# LN2_Autofill_Controller.net
KiCad netlist of a schematic drawn in EAGLE
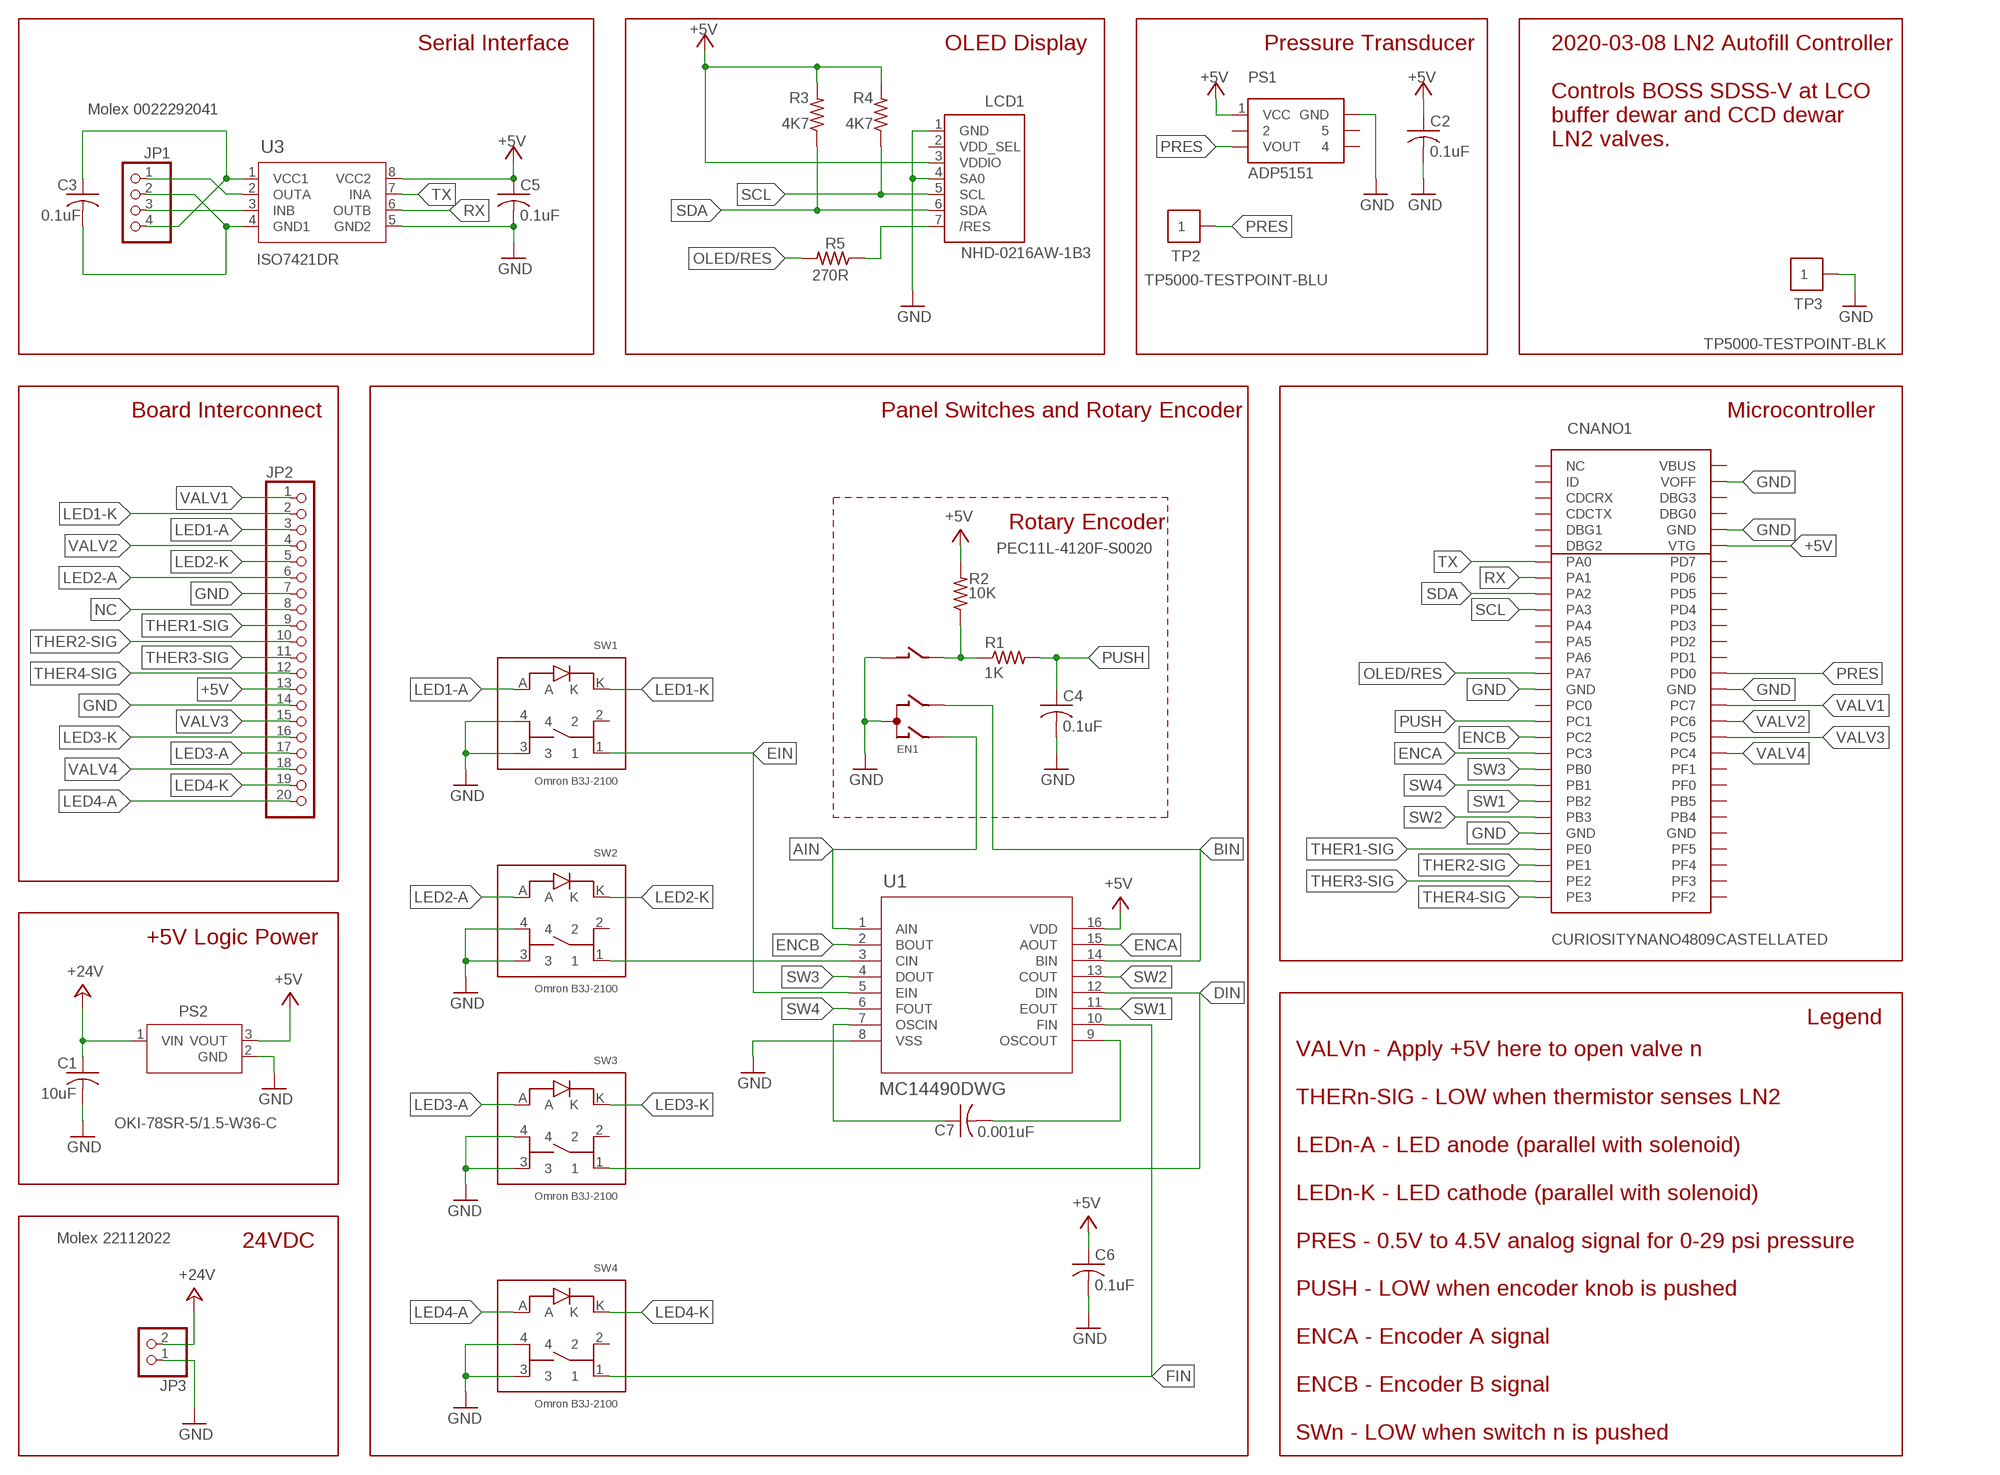
[diagram p0: schematic, sheet 1]

(export (version "E")
  (design (tool "Eeschema 10.0.6"))
  (components
    (comp (ref "C1")
      (value "10uF")
      (footprint "eagle-import:C1210K")
      (libsource (lib "eagle-import") (part "C-USC1210K"))
    )
    (comp (ref "C2")
      (value "0.1uF")
      (footprint "eagle-import:C0805")
      (libsource (lib "eagle-import") (part "C-USC0805"))
    )
    (comp (ref "C3")
      (value "0.1uF")
      (footprint "eagle-import:C0805")
      (libsource (lib "eagle-import") (part "C-USC0805"))
    )
    (comp (ref "C4")
      (value "0.1uF")
      (footprint "eagle-import:C0805")
      (libsource (lib "eagle-import") (part "C-USC0805"))
    )
    (comp (ref "C5")
      (value "0.1uF")
      (footprint "eagle-import:C0805")
      (libsource (lib "eagle-import") (part "C-USC0805"))
    )
    (comp (ref "C6")
      (value "0.1uF")
      (footprint "eagle-import:C0805")
      (libsource (lib "eagle-import") (part "C-USC0805"))
    )
    (comp (ref "C7")
      (value "0.001uF")
      (footprint "eagle-import:C0805")
      (libsource (lib "eagle-import") (part "C-USC0805"))
    )
    (comp (ref "CNANO1")
      (value "CURIOSITYNANO4809CASTELLATED")
      (footprint "eagle-import:CURIOSITYNANO4809CASTELLATED")
      (libsource (lib "eagle-import") (part "CURIOSITYNANO4809CASTELLATED"))
    )
    (comp (ref "EN1")
      (value "PEC11L-4120F-S0020")
      (footprint "eagle-import:ENC-BOURNES-PEC11L")
      (libsource (lib "eagle-import") (part "ENC-BOURNES-PEC11L"))
    )
    (comp (ref "JP1")
      (value "Molex 0022292041")
      (footprint "eagle-import:MOLEX-04-VERT")
      (libsource (lib "eagle-import") (part "PINHD-1X4MOLEX-04-VERT"))
    )
    (comp (ref "JP2")
      (value "PINHD-1X20")
      (footprint "eagle-import:1X20")
      (libsource (lib "eagle-import") (part "PINHD-1X20"))
    )
    (comp (ref "JP3")
      (value "Molex 22112022")
      (footprint "eagle-import:MOLEX-02-VERT")
      (libsource (lib "eagle-import") (part "PINHD-1X2MOLEX-02-VERT"))
    )
    (comp (ref "LCD1")
      (value "NHD-0216AW-1B3")
      (footprint "eagle-import:LCD-NEWHAVEN-16X2")
      (libsource (lib "eagle-import") (part "LCD-NEWHAVEN-16X2"))
    )
    (comp (ref "PS1")
      (value "ADP5151")
      (footprint "eagle-import:PRESSURE-SENSOR-ADP5151")
      (libsource (lib "eagle-import") (part "PRESSURE-SENSOR-ADP5151"))
    )
    (comp (ref "PS2")
      (value "OKI-78SR-5/1.5-W36-C")
      (footprint "eagle-import:CONV_OKI-78SR-5_1.5-W36-C")
      (fields
        (field (name "DIGI-KEY_PART_NUMBER") "811-2196-5-ND")
        (field (name "MF") "Murata Power Solutions Inc.")
      )
      (libsource (lib "eagle-import") (part "OKI-78SR-5/1.5-W36-C"))
    )
    (comp (ref "R1")
      (value "1K")
      (footprint "eagle-import:R0805")
      (libsource (lib "eagle-import") (part "R-US_R0805"))
    )
    (comp (ref "R2")
      (value "10K")
      (footprint "eagle-import:R0805")
      (libsource (lib "eagle-import") (part "R-US_R0805"))
    )
    (comp (ref "R3")
      (value "4K7")
      (footprint "eagle-import:R0805")
      (libsource (lib "eagle-import") (part "R-US_R0805"))
    )
    (comp (ref "R4")
      (value "4K7")
      (footprint "eagle-import:R0805")
      (libsource (lib "eagle-import") (part "R-US_R0805"))
    )
    (comp (ref "R5")
      (value "270R")
      (footprint "eagle-import:R0805")
      (libsource (lib "eagle-import") (part "R-US_R0805"))
    )
    (comp (ref "SW1")
      (value "Omron B3J-2100")
      (footprint "eagle-import:SWITCH-OMRON-B3J-1LED")
      (libsource (lib "eagle-import") (part "SWITCH-OMRON-B3J-1LED"))
    )
    (comp (ref "SW2")
      (value "Omron B3J-2100")
      (footprint "eagle-import:SWITCH-OMRON-B3J-1LED")
      (libsource (lib "eagle-import") (part "SWITCH-OMRON-B3J-1LED"))
    )
    (comp (ref "SW3")
      (value "Omron B3J-2100")
      (footprint "eagle-import:SWITCH-OMRON-B3J-1LED")
      (libsource (lib "eagle-import") (part "SWITCH-OMRON-B3J-1LED"))
    )
    (comp (ref "SW4")
      (value "Omron B3J-2100")
      (footprint "eagle-import:SWITCH-OMRON-B3J-1LED")
      (libsource (lib "eagle-import") (part "SWITCH-OMRON-B3J-1LED"))
    )
    (comp (ref "TP2")
      (value "TP5000-TESTPOINT-BLU")
      (footprint "eagle-import:TP5000-TESTPOINT-BLU")
      (libsource (lib "eagle-import") (part "TP5000-TESTPOINT-BLU"))
    )
    (comp (ref "TP3")
      (value "TP5000-TESTPOINT-BLK")
      (footprint "eagle-import:TP5000-TESTPOINT-BLK")
      (libsource (lib "eagle-import") (part "TP5000-TESTPOINT-BLK"))
    )
    (comp (ref "U1")
      (value "MC14490DWG")
      (footprint "eagle-import:SOIC127P1030X265-16N")
      (libsource (lib "eagle-import") (part "DEBOUNCER-MC14490DWGSOIC-16-WB"))
    )
    (comp (ref "U3")
      (value "ISO7421DR")
      (footprint "eagle-import:SOIC127P599X175-8N")
      (libsource (lib "eagle-import") (part "ISO7421DRTI-SOIC-D8"))
    )
  )
  (nets
    (net (code "1") (name "+5V") (class "Default")
      (node (ref "C2") (pin "1") (pinfunction "1_1") (pintype "passive"))
      (node (ref "C5") (pin "1") (pinfunction "1_1") (pintype "passive"))
      (node (ref "C6") (pin "1") (pinfunction "1_1") (pintype "passive"))
      (node (ref "CNANO1") (pin "VTG") (pinfunction "VTG_VTG") (pintype "bidirectional"))
      (node (ref "JP2") (pin "13") (pinfunction "13_13") (pintype "passive"))
      (node (ref "LCD1") (pin "3") (pinfunction "VDDIO_3") (pintype "bidirectional"))
      (node (ref "PS1") (pin "1") (pinfunction "VCC_1") (pintype "bidirectional"))
      (node (ref "PS2") (pin "3") (pinfunction "VOUT_3") (pintype "power_in"))
      (node (ref "R2") (pin "2") (pinfunction "2_2") (pintype "passive"))
      (node (ref "R3") (pin "2") (pinfunction "2_2") (pintype "passive"))
      (node (ref "R4") (pin "2") (pinfunction "2_2") (pintype "passive"))
      (node (ref "U1") (pin "16") (pinfunction "VDD_16") (pintype "power_in"))
      (node (ref "U3") (pin "8") (pinfunction "VCC2_8") (pintype "power_in"))
    )
    (net (code "2") (name "+24V") (class "Default")
      (node (ref "C1") (pin "1") (pinfunction "1_1") (pintype "passive"))
      (node (ref "JP3") (pin "2") (pinfunction "2_2") (pintype "passive"))
      (node (ref "PS2") (pin "1") (pinfunction "VIN_1") (pintype "input"))
    )
    (net (code "3") (name "AIN") (class "Default")
      (node (ref "EN1") (pin "A") (pinfunction "A_A") (pintype "passive"))
      (node (ref "U1") (pin "1") (pinfunction "AIN_1") (pintype "input"))
    )
    (net (code "4") (name "BIN") (class "Default")
      (node (ref "EN1") (pin "B") (pinfunction "B_B") (pintype "passive"))
      (node (ref "U1") (pin "14") (pinfunction "BIN_14") (pintype "input"))
    )
    (net (code "5") (name "DIN") (class "Default")
      (node (ref "SW3") (pin "1") (pinfunction "1_1") (pintype "bidirectional"))
      (node (ref "U1") (pin "12") (pinfunction "DIN_12") (pintype "input"))
    )
    (net (code "6") (name "EIN") (class "Default")
      (node (ref "SW1") (pin "1") (pinfunction "1_1") (pintype "bidirectional"))
      (node (ref "U1") (pin "5") (pinfunction "EIN_5") (pintype "input"))
    )
    (net (code "7") (name "ENCA") (class "Default")
      (node (ref "CNANO1") (pin "PC3") (pinfunction "PC3_PC3") (pintype "bidirectional"))
      (node (ref "U1") (pin "15") (pinfunction "AOUT_15") (pintype "output"))
    )
    (net (code "8") (name "ENCB") (class "Default")
      (node (ref "CNANO1") (pin "PC2") (pinfunction "PC2_PC2") (pintype "bidirectional"))
      (node (ref "U1") (pin "2") (pinfunction "BOUT_2") (pintype "output"))
    )
    (net (code "9") (name "FIN") (class "Default")
      (node (ref "SW4") (pin "1") (pinfunction "1_1") (pintype "bidirectional"))
      (node (ref "U1") (pin "10") (pinfunction "FIN_10") (pintype "input"))
    )
    (net (code "10") (name "GND") (class "Default")
      (node (ref "C1") (pin "2") (pinfunction "2_2") (pintype "passive"))
      (node (ref "C2") (pin "2") (pinfunction "2_2") (pintype "passive"))
      (node (ref "C4") (pin "2") (pinfunction "2_2") (pintype "passive"))
      (node (ref "C5") (pin "2") (pinfunction "2_2") (pintype "passive"))
      (node (ref "C6") (pin "2") (pinfunction "2_2") (pintype "passive"))
      (node (ref "CNANO1") (pin "GND15") (pinfunction "GND_GND15") (pintype "bidirectional"))
      (node (ref "CNANO1") (pin "GND24") (pinfunction "GND_GND24") (pintype "bidirectional"))
      (node (ref "CNANO1") (pin "GND42") (pinfunction "GND_GND42") (pintype "bidirectional"))
      (node (ref "CNANO1") (pin "GND52") (pinfunction "GND_GND52") (pintype "bidirectional"))
      (node (ref "CNANO1") (pin "VOFF") (pinfunction "VOFF_VOFF") (pintype "bidirectional"))
      (node (ref "EN1") (pin "2") (pinfunction "C1_2") (pintype "passive"))
      (node (ref "EN1") (pin "C") (pinfunction "C_C") (pintype "passive"))
      (node (ref "JP2") (pin "14") (pinfunction "14_14") (pintype "passive"))
      (node (ref "JP2") (pin "7") (pinfunction "7_7") (pintype "passive"))
      (node (ref "JP3") (pin "1") (pinfunction "1_1") (pintype "passive"))
      (node (ref "LCD1") (pin "1") (pinfunction "GND_1") (pintype "bidirectional"))
      (node (ref "LCD1") (pin "4") (pinfunction "SA0_4") (pintype "bidirectional"))
      (node (ref "PS1") (pin "6") (pinfunction "GND_6") (pintype "bidirectional"))
      (node (ref "PS2") (pin "2") (pinfunction "GND_2") (pintype "power_in"))
      (node (ref "SW1") (pin "3") (pinfunction "3_3") (pintype "bidirectional"))
      (node (ref "SW1") (pin "4") (pinfunction "4_4") (pintype "bidirectional"))
      (node (ref "SW2") (pin "3") (pinfunction "3_3") (pintype "bidirectional"))
      (node (ref "SW2") (pin "4") (pinfunction "4_4") (pintype "bidirectional"))
      (node (ref "SW3") (pin "3") (pinfunction "3_3") (pintype "bidirectional"))
      (node (ref "SW3") (pin "4") (pinfunction "4_4") (pintype "bidirectional"))
      (node (ref "SW4") (pin "3") (pinfunction "3_3") (pintype "bidirectional"))
      (node (ref "SW4") (pin "4") (pinfunction "4_4") (pintype "bidirectional"))
      (node (ref "TP3") (pin "P$1") (pinfunction "1_P$1") (pintype "bidirectional"))
      (node (ref "U1") (pin "8") (pinfunction "VSS_8") (pintype "power_in"))
      (node (ref "U3") (pin "5") (pinfunction "GND2_5") (pintype "power_in"))
    )
    (net (code "11") (name "LED1-A") (class "Default")
      (node (ref "JP2") (pin "3") (pinfunction "3_3") (pintype "passive"))
      (node (ref "SW1") (pin "A") (pinfunction "A_A") (pintype "bidirectional"))
    )
    (net (code "12") (name "LED1-K") (class "Default")
      (node (ref "JP2") (pin "2") (pinfunction "2_2") (pintype "passive"))
      (node (ref "SW1") (pin "K") (pinfunction "K_K") (pintype "bidirectional"))
    )
    (net (code "13") (name "LED2-A") (class "Default")
      (node (ref "JP2") (pin "6") (pinfunction "6_6") (pintype "passive"))
      (node (ref "SW2") (pin "A") (pinfunction "A_A") (pintype "bidirectional"))
    )
    (net (code "14") (name "LED2-K") (class "Default")
      (node (ref "JP2") (pin "5") (pinfunction "5_5") (pintype "passive"))
      (node (ref "SW2") (pin "K") (pinfunction "K_K") (pintype "bidirectional"))
    )
    (net (code "15") (name "LED3-A") (class "Default")
      (node (ref "JP2") (pin "17") (pinfunction "17_17") (pintype "passive"))
      (node (ref "SW3") (pin "A") (pinfunction "A_A") (pintype "bidirectional"))
    )
    (net (code "16") (name "LED3-K") (class "Default")
      (node (ref "JP2") (pin "16") (pinfunction "16_16") (pintype "passive"))
      (node (ref "SW3") (pin "K") (pinfunction "K_K") (pintype "bidirectional"))
    )
    (net (code "17") (name "LED4-A") (class "Default")
      (node (ref "JP2") (pin "20") (pinfunction "20_20") (pintype "passive"))
      (node (ref "SW4") (pin "A") (pinfunction "A_A") (pintype "bidirectional"))
    )
    (net (code "18") (name "LED4-K") (class "Default")
      (node (ref "JP2") (pin "19") (pinfunction "19_19") (pintype "passive"))
      (node (ref "SW4") (pin "K") (pinfunction "K_K") (pintype "bidirectional"))
    )
    (net (code "19") (name "NC") (class "Default")
      (node (ref "JP2") (pin "8") (pinfunction "8_8") (pintype "passive"))
    )
    (net (code "20") (name "Net-(EN1-B1)") (class "Default")
      (node (ref "EN1") (pin "1") (pinfunction "B1_1") (pintype "passive"))
      (node (ref "R1") (pin "1") (pinfunction "1_1") (pintype "passive"))
      (node (ref "R2") (pin "1") (pinfunction "1_1") (pintype "passive"))
    )
    (net (code "21") (name "Net-(LCD1-{slash}RES)") (class "Default")
      (node (ref "LCD1") (pin "7") (pinfunction "/RES_7") (pintype "bidirectional"))
      (node (ref "R5") (pin "1") (pinfunction "1_1") (pintype "passive"))
    )
    (net (code "22") (name "Net-(U1-CIN)") (class "Default")
      (node (ref "SW2") (pin "1") (pinfunction "1_1") (pintype "bidirectional"))
      (node (ref "U1") (pin "3") (pinfunction "CIN_3") (pintype "input"))
    )
    (net (code "23") (name "Net-(U1-OSCIN)") (class "Default")
      (node (ref "C7") (pin "1") (pinfunction "1_1") (pintype "passive"))
      (node (ref "U1") (pin "7") (pinfunction "OSCIN_7") (pintype "input"))
    )
    (net (code "24") (name "Net-(U1-OSCOUT)") (class "Default")
      (node (ref "C7") (pin "2") (pinfunction "2_2") (pintype "passive"))
      (node (ref "U1") (pin "9") (pinfunction "OSCOUT_9") (pintype "output"))
    )
    (net (code "25") (name "Net-(U3-GND1)") (class "Default")
      (node (ref "C3") (pin "2") (pinfunction "2_2") (pintype "passive"))
      (node (ref "JP1") (pin "2") (pinfunction "2_2") (pintype "passive"))
      (node (ref "U3") (pin "4") (pinfunction "GND1_4") (pintype "power_in"))
    )
    (net (code "26") (name "Net-(U3-INB)") (class "Default")
      (node (ref "JP1") (pin "3") (pinfunction "3_3") (pintype "passive"))
      (node (ref "U3") (pin "3") (pinfunction "INB_3") (pintype "input"))
    )
    (net (code "27") (name "Net-(U3-OUTA)") (class "Default")
      (node (ref "JP1") (pin "1") (pinfunction "1_1") (pintype "passive"))
      (node (ref "U3") (pin "2") (pinfunction "OUTA_2") (pintype "output"))
    )
    (net (code "28") (name "Net-(U3-VCC1)") (class "Default")
      (node (ref "C3") (pin "1") (pinfunction "1_1") (pintype "passive"))
      (node (ref "JP1") (pin "4") (pinfunction "4_4") (pintype "passive"))
      (node (ref "U3") (pin "1") (pinfunction "VCC1_1") (pintype "power_in"))
    )
    (net (code "29") (name "OLED{slash}RES") (class "Default")
      (node (ref "CNANO1") (pin "PA7-SS") (pinfunction "PA7_PA7-SS") (pintype "bidirectional"))
      (node (ref "R5") (pin "2") (pinfunction "2_2") (pintype "passive"))
    )
    (net (code "30") (name "PRES") (class "Default")
      (node (ref "CNANO1") (pin "PD0-AIN0") (pinfunction "PD0_PD0-AIN0") (pintype "bidirectional"))
      (node (ref "PS1") (pin "3") (pinfunction "VOUT_3") (pintype "bidirectional"))
      (node (ref "TP2") (pin "P$1") (pinfunction "1_P$1") (pintype "bidirectional"))
    )
    (net (code "31") (name "PUSH") (class "Default")
      (node (ref "C4") (pin "1") (pinfunction "1_1") (pintype "passive"))
      (node (ref "CNANO1") (pin "PC1-RX") (pinfunction "PC1_PC1-RX") (pintype "bidirectional"))
      (node (ref "R1") (pin "2") (pinfunction "2_2") (pintype "passive"))
    )
    (net (code "32") (name "RX") (class "Default")
      (node (ref "CNANO1") (pin "PA1-RX") (pinfunction "PA1_PA1-RX") (pintype "bidirectional"))
      (node (ref "U3") (pin "6") (pinfunction "OUTB_6") (pintype "output"))
    )
    (net (code "33") (name "SCL") (class "Default")
      (node (ref "CNANO1") (pin "PA3-SCL") (pinfunction "PA3_PA3-SCL") (pintype "bidirectional"))
      (node (ref "LCD1") (pin "5") (pinfunction "SCL_5") (pintype "bidirectional"))
      (node (ref "R4") (pin "1") (pinfunction "1_1") (pintype "passive"))
    )
    (net (code "34") (name "SDA") (class "Default")
      (node (ref "CNANO1") (pin "PA2-SDA") (pinfunction "PA2_PA2-SDA") (pintype "bidirectional"))
      (node (ref "LCD1") (pin "6") (pinfunction "SDA_6") (pintype "bidirectional"))
      (node (ref "R3") (pin "1") (pinfunction "1_1") (pintype "passive"))
    )
    (net (code "35") (name "SW1") (class "Default")
      (node (ref "CNANO1") (pin "PB2") (pinfunction "PB2_PB2") (pintype "bidirectional"))
      (node (ref "U1") (pin "11") (pinfunction "EOUT_11") (pintype "output"))
    )
    (net (code "36") (name "SW2") (class "Default")
      (node (ref "CNANO1") (pin "PB3") (pinfunction "PB3_PB3") (pintype "bidirectional"))
      (node (ref "U1") (pin "13") (pinfunction "COUT_13") (pintype "output"))
    )
    (net (code "37") (name "SW3") (class "Default")
      (node (ref "CNANO1") (pin "PB0-TX") (pinfunction "PB0_PB0-TX") (pintype "bidirectional"))
      (node (ref "U1") (pin "4") (pinfunction "DOUT_4") (pintype "output"))
    )
    (net (code "38") (name "SW4") (class "Default")
      (node (ref "CNANO1") (pin "PB1-RX") (pinfunction "PB1_PB1-RX") (pintype "bidirectional"))
      (node (ref "U1") (pin "6") (pinfunction "FOUT_6") (pintype "output"))
    )
    (net (code "39") (name "THER1-SIG") (class "Default")
      (node (ref "CNANO1") (pin "PE0") (pinfunction "PE0_PE0") (pintype "bidirectional"))
      (node (ref "JP2") (pin "9") (pinfunction "9_9") (pintype "passive"))
    )
    (net (code "40") (name "THER2-SIG") (class "Default")
      (node (ref "CNANO1") (pin "PE1") (pinfunction "PE1_PE1") (pintype "bidirectional"))
      (node (ref "JP2") (pin "10") (pinfunction "10_10") (pintype "passive"))
    )
    (net (code "41") (name "THER3-SIG") (class "Default")
      (node (ref "CNANO1") (pin "PE2") (pinfunction "PE2_PE2") (pintype "bidirectional"))
      (node (ref "JP2") (pin "11") (pinfunction "11_11") (pintype "passive"))
    )
    (net (code "42") (name "THER4-SIG") (class "Default")
      (node (ref "CNANO1") (pin "PE3") (pinfunction "PE3_PE3") (pintype "bidirectional"))
      (node (ref "JP2") (pin "12") (pinfunction "12_12") (pintype "passive"))
    )
    (net (code "43") (name "TX") (class "Default")
      (node (ref "CNANO1") (pin "PA0-TX") (pinfunction "PA0_PA0-TX") (pintype "bidirectional"))
      (node (ref "U3") (pin "7") (pinfunction "INA_7") (pintype "input"))
    )
    (net (code "44") (name "VALV1") (class "Default")
      (node (ref "CNANO1") (pin "PC7") (pinfunction "PC7_PC7") (pintype "bidirectional"))
      (node (ref "JP2") (pin "1") (pinfunction "1_1") (pintype "passive"))
    )
    (net (code "45") (name "VALV2") (class "Default")
      (node (ref "CNANO1") (pin "PC6") (pinfunction "PC6_PC6") (pintype "bidirectional"))
      (node (ref "JP2") (pin "4") (pinfunction "4_4") (pintype "passive"))
    )
    (net (code "46") (name "VALV3") (class "Default")
      (node (ref "CNANO1") (pin "PC5") (pinfunction "PC5_PC5") (pintype "bidirectional"))
      (node (ref "JP2") (pin "15") (pinfunction "15_15") (pintype "passive"))
    )
    (net (code "47") (name "VALV4") (class "Default")
      (node (ref "CNANO1") (pin "PC4") (pinfunction "PC4_PC4") (pintype "bidirectional"))
      (node (ref "JP2") (pin "18") (pinfunction "18_18") (pintype "passive"))
    )
    (net (code "48") (name "unconnected-(CNANO1-CDCRX-PadPB0-RX)") (class "Default")
      (node (ref "CNANO1") (pin "PB0-RX") (pinfunction "CDCRX_PB0-RX") (pintype "bidirectional"))
    )
    (net (code "49") (name "unconnected-(CNANO1-CDCTX-PadPB1-TX)") (class "Default")
      (node (ref "CNANO1") (pin "PB1-TX") (pinfunction "CDCTX_PB1-TX") (pintype "bidirectional"))
    )
    (net (code "50") (name "unconnected-(CNANO1-DBG0-PadUPDI)") (class "Default")
      (node (ref "CNANO1") (pin "UPDI") (pinfunction "DBG0_UPDI") (pintype "bidirectional"))
    )
    (net (code "51") (name "unconnected-(CNANO1-DBG1-PadPF3-5)") (class "Default")
      (node (ref "CNANO1") (pin "PF3-5") (pinfunction "DBG1_PF3-5") (pintype "bidirectional"))
    )
    (net (code "52") (name "unconnected-(CNANO1-DBG2-PadPF2-6)") (class "Default")
      (node (ref "CNANO1") (pin "PF2-6") (pinfunction "DBG2_PF2-6") (pintype "bidirectional"))
    )
    (net (code "53") (name "unconnected-(CNANO1-DBG3-PadPF6-SW0)") (class "Default")
      (node (ref "CNANO1") (pin "PF6-SW0") (pinfunction "DBG3_PF6-SW0") (pintype "bidirectional"))
    )
    (net (code "54") (name "unconnected-(CNANO1-GND-PadGND33)") (class "Default")
      (node (ref "CNANO1") (pin "GND33") (pinfunction "GND_GND33") (pintype "bidirectional"))
    )
    (net (code "55") (name "unconnected-(CNANO1-PA4-PadPA4-MOSI)") (class "Default")
      (node (ref "CNANO1") (pin "PA4-MOSI") (pinfunction "PA4_PA4-MOSI") (pintype "bidirectional"))
    )
    (net (code "56") (name "unconnected-(CNANO1-PA5-PadPA5-MISO)") (class "Default")
      (node (ref "CNANO1") (pin "PA5-MISO") (pinfunction "PA5_PA5-MISO") (pintype "bidirectional"))
    )
    (net (code "57") (name "unconnected-(CNANO1-PA6-PadPA6-SCK)") (class "Default")
      (node (ref "CNANO1") (pin "PA6-SCK") (pinfunction "PA6_PA6-SCK") (pintype "bidirectional"))
    )
    (net (code "58") (name "unconnected-(CNANO1-PC0-PadPC0-TX)") (class "Default")
      (node (ref "CNANO1") (pin "PC0-TX") (pinfunction "PC0_PC0-TX") (pintype "bidirectional"))
    )
    (net (code "59") (name "unconnected-(CNANO1-PD1-PadPD1-AIN1)") (class "Default")
      (node (ref "CNANO1") (pin "PD1-AIN1") (pinfunction "PD1_PD1-AIN1") (pintype "bidirectional"))
    )
    (net (code "60") (name "unconnected-(CNANO1-PD2-PadPD2-AIN2)") (class "Default")
      (node (ref "CNANO1") (pin "PD2-AIN2") (pinfunction "PD2_PD2-AIN2") (pintype "bidirectional"))
    )
    (net (code "61") (name "unconnected-(CNANO1-PD3-PadPD3-AIN3)") (class "Default")
      (node (ref "CNANO1") (pin "PD3-AIN3") (pinfunction "PD3_PD3-AIN3") (pintype "bidirectional"))
    )
    (net (code "62") (name "unconnected-(CNANO1-PD4-PadPD4-AIN4)") (class "Default")
      (node (ref "CNANO1") (pin "PD4-AIN4") (pinfunction "PD4_PD4-AIN4") (pintype "bidirectional"))
    )
    (net (code "63") (name "unconnected-(CNANO1-PD5-PadPD5-AIN5)") (class "Default")
      (node (ref "CNANO1") (pin "PD5-AIN5") (pinfunction "PD5_PD5-AIN5") (pintype "bidirectional"))
    )
    (net (code "64") (name "unconnected-(CNANO1-PD6-PadPD6-AIN6)") (class "Default")
      (node (ref "CNANO1") (pin "PD6-AIN6") (pinfunction "PD6_PD6-AIN6") (pintype "bidirectional"))
    )
    (net (code "65") (name "unconnected-(CNANO1-PD7-PadPD7-AIN7)") (class "Default")
      (node (ref "CNANO1") (pin "PD7-AIN7") (pinfunction "PD7_PD7-AIN7") (pintype "bidirectional"))
    )
    (net (code "66") (name "unconnected-(CNANO1-PF0-PadPF0-TOSC1)") (class "Default")
      (node (ref "CNANO1") (pin "PF0-TOSC1") (pinfunction "PF0_PF0-TOSC1") (pintype "bidirectional"))
    )
    (net (code "67") (name "unconnected-(CNANO1-PF1-PadPF1-TOSC2)") (class "Default")
      (node (ref "CNANO1") (pin "PF1-TOSC2") (pinfunction "PF1_PF1-TOSC2") (pintype "bidirectional"))
    )
    (net (code "68") (name "unconnected-(CNANO1-PF5-PadPF5-LED)") (class "Default")
      (node (ref "CNANO1") (pin "PF5-LED") (pinfunction "PF5_PF5-LED") (pintype "bidirectional"))
    )
    (net (code "69") (name "unconnected-(CNANO1-PadID)") (class "Default")
      (node (ref "CNANO1") (pin "ID") (pinfunction "ID_ID") (pintype "bidirectional"))
    )
    (net (code "70") (name "unconnected-(CNANO1-PadNC)") (class "Default")
      (node (ref "CNANO1") (pin "NC") (pinfunction "NC_NC") (pintype "bidirectional"))
    )
    (net (code "71") (name "unconnected-(CNANO1-PadPB4)") (class "Default")
      (node (ref "CNANO1") (pin "PB4") (pinfunction "PB4_PB4") (pintype "bidirectional"))
    )
    (net (code "72") (name "unconnected-(CNANO1-PadPB5)") (class "Default")
      (node (ref "CNANO1") (pin "PB5") (pinfunction "PB5_PB5") (pintype "bidirectional"))
    )
    (net (code "73") (name "unconnected-(CNANO1-PadPF2)") (class "Default")
      (node (ref "CNANO1") (pin "PF2") (pinfunction "PF2_PF2") (pintype "bidirectional"))
    )
    (net (code "74") (name "unconnected-(CNANO1-PadPF3)") (class "Default")
      (node (ref "CNANO1") (pin "PF3") (pinfunction "PF3_PF3") (pintype "bidirectional"))
    )
    (net (code "75") (name "unconnected-(CNANO1-PadPF4)") (class "Default")
      (node (ref "CNANO1") (pin "PF4") (pinfunction "PF4_PF4") (pintype "bidirectional"))
    )
    (net (code "76") (name "unconnected-(CNANO1-PadVBUS)") (class "Default")
      (node (ref "CNANO1") (pin "VBUS") (pinfunction "VBUS_VBUS") (pintype "bidirectional"))
    )
    (net (code "77") (name "unconnected-(LCD1-VDD_SEL-Pad2)") (class "Default")
      (node (ref "LCD1") (pin "2") (pinfunction "VDD_SEL_2") (pintype "bidirectional"))
    )
    (net (code "78") (name "unconnected-(PS1-Pad2)") (class "Default")
      (node (ref "PS1") (pin "2") (pinfunction "2_2") (pintype "bidirectional"))
    )
    (net (code "79") (name "unconnected-(PS1-Pad4)") (class "Default")
      (node (ref "PS1") (pin "4") (pinfunction "4_4") (pintype "bidirectional"))
    )
    (net (code "80") (name "unconnected-(PS1-Pad5)") (class "Default")
      (node (ref "PS1") (pin "5") (pinfunction "5_5") (pintype "bidirectional"))
    )
    (net (code "81") (name "unconnected-(SW1-Pad2)") (class "Default")
      (node (ref "SW1") (pin "2") (pinfunction "2_2") (pintype "bidirectional"))
    )
    (net (code "82") (name "unconnected-(SW2-Pad2)") (class "Default")
      (node (ref "SW2") (pin "2") (pinfunction "2_2") (pintype "bidirectional"))
    )
    (net (code "83") (name "unconnected-(SW3-Pad2)") (class "Default")
      (node (ref "SW3") (pin "2") (pinfunction "2_2") (pintype "bidirectional"))
    )
    (net (code "84") (name "unconnected-(SW4-Pad2)") (class "Default")
      (node (ref "SW4") (pin "2") (pinfunction "2_2") (pintype "bidirectional"))
    )
  )
)
